# MCU.net
KiCad netlist of a schematic drawn in Altium Designer
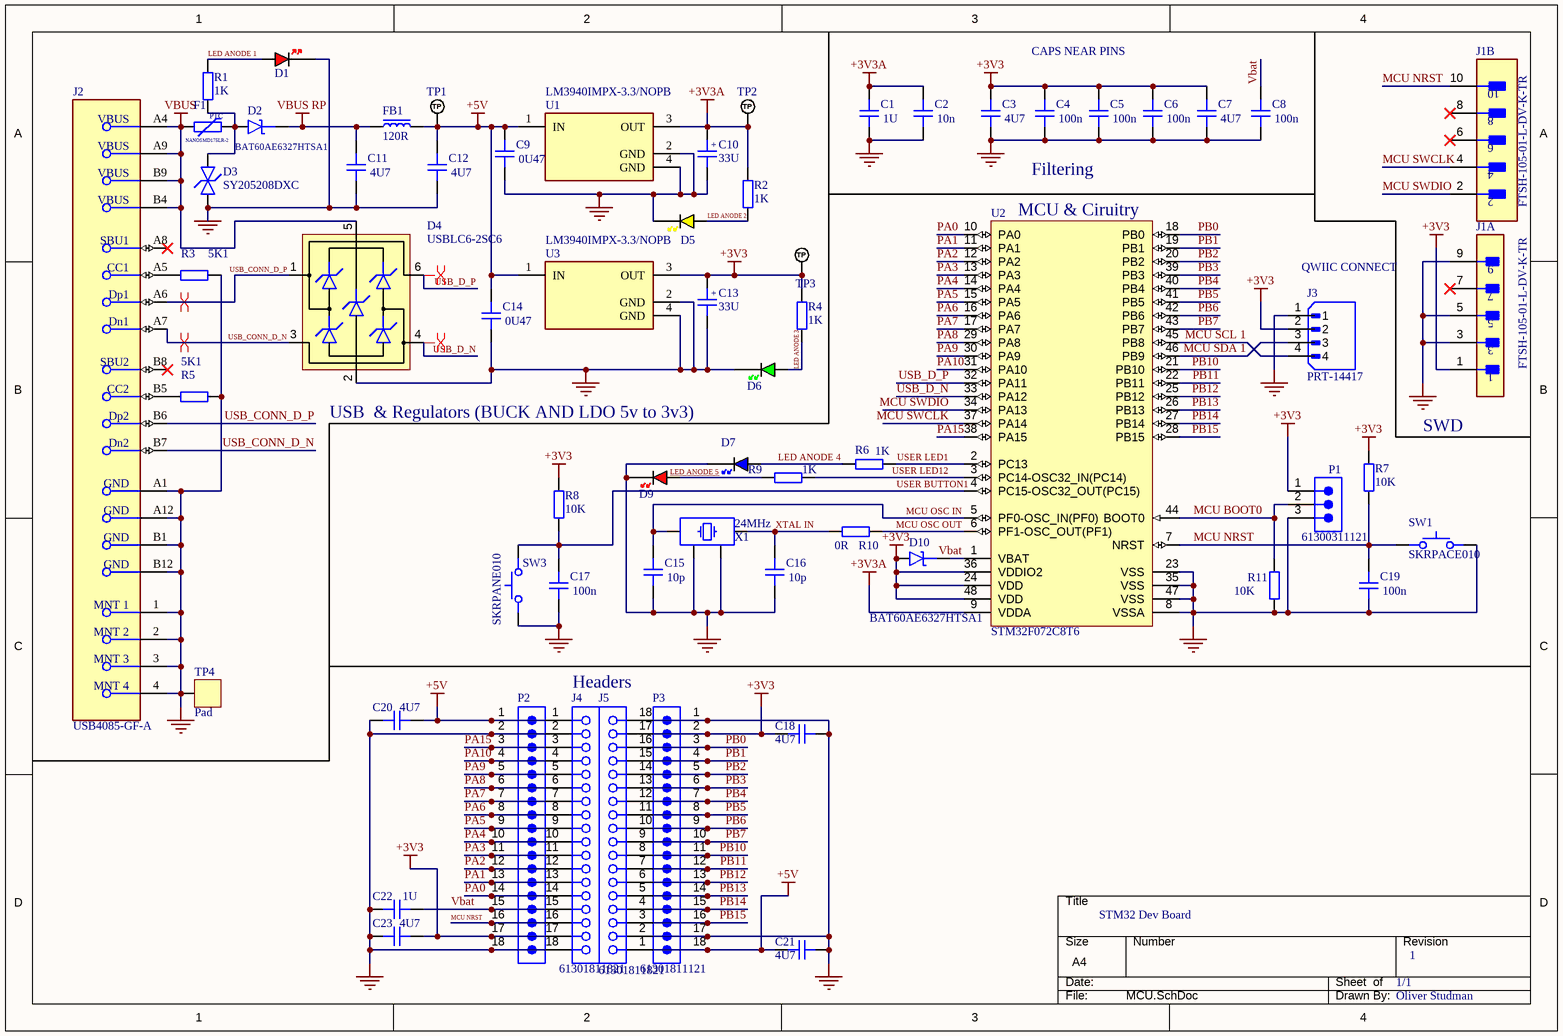
[diagram p0: MCU.SchDoc]

(export (version "E")
  (design (tool "Eeschema 10.0.6"))
  (components
    (comp (ref "C1")
      (value "1U")
      (footprint "CAP_0603")
      (description "Capacitor SMD 0603")
      (libsource (lib "Schematic-Lib-PhilsLab") (part "CAP_0603"))
    )
    (comp (ref "C2")
      (value "10n")
      (footprint "CAP_0603")
      (description "Capacitor SMD 0603")
      (libsource (lib "Schematic-Lib-PhilsLab") (part "CAP_0603"))
    )
    (comp (ref "C3")
      (value "4U7")
      (footprint "CAP_0603")
      (description "Capacitor SMD 0603")
      (libsource (lib "Schematic-Lib-PhilsLab") (part "CAP_0603"))
    )
    (comp (ref "C4")
      (value "100n")
      (footprint "CAP_0603")
      (description "Capacitor SMD 0603")
      (libsource (lib "Schematic-Lib-PhilsLab") (part "CAP_0603"))
    )
    (comp (ref "C5")
      (value "100n")
      (footprint "CAP_0603")
      (description "Capacitor SMD 0603")
      (libsource (lib "Schematic-Lib-PhilsLab") (part "CAP_0603"))
    )
    (comp (ref "C6")
      (value "100n")
      (footprint "CAP_0603")
      (description "Capacitor SMD 0603")
      (libsource (lib "Schematic-Lib-PhilsLab") (part "CAP_0603"))
    )
    (comp (ref "C7")
      (value "4U7")
      (footprint "CAP_0603")
      (description "Capacitor SMD 0603")
      (libsource (lib "Schematic-Lib-PhilsLab") (part "CAP_0603"))
    )
    (comp (ref "C8")
      (value "100n")
      (footprint "CAP_0603")
      (description "Capacitor SMD 0603")
      (libsource (lib "Schematic-Lib-PhilsLab") (part "CAP_0603"))
    )
    (comp (ref "C9")
      (value "0U47")
      (footprint "CAP_0603")
      (description "Capacitor SMD 0603")
      (libsource (lib "Schematic-Lib-PhilsLab") (part "CAP_0603"))
    )
    (comp (ref "C10")
      (value "33U")
      (footprint "CAP_TANT_0603")
      (description "Capacitor SMD Tantalum 0603")
      (libsource (lib "Schematic-Lib-PhilsLab") (part "CAP_TANT_0603"))
    )
    (comp (ref "C11")
      (value "4U7")
      (footprint "CAP_0603")
      (description "Capacitor SMD 0603")
      (libsource (lib "Schematic-Lib-PhilsLab") (part "CAP_0603"))
    )
    (comp (ref "C12")
      (value "4U7")
      (footprint "CAP_0603")
      (description "Capacitor SMD 0603")
      (libsource (lib "Schematic-Lib-PhilsLab") (part "CAP_0603"))
    )
    (comp (ref "C13")
      (value "33U")
      (footprint "CAP_TANT_0603")
      (description "Capacitor SMD Tantalum 0603")
      (libsource (lib "Schematic-Lib-PhilsLab") (part "CAP_TANT_0603"))
    )
    (comp (ref "C14")
      (value "0U47")
      (footprint "CAP_0603")
      (description "Capacitor SMD 0603")
      (libsource (lib "Schematic-Lib-PhilsLab") (part "CAP_0603"))
    )
    (comp (ref "C15")
      (value "10p")
      (footprint "CAP_0603")
      (description "Capacitor SMD 0603")
      (libsource (lib "Schematic-Lib-PhilsLab") (part "CAP_0603"))
    )
    (comp (ref "C16")
      (value "10p")
      (footprint "CAP_0603")
      (description "Capacitor SMD 0603")
      (libsource (lib "Schematic-Lib-PhilsLab") (part "CAP_0603"))
    )
    (comp (ref "C17")
      (value "100n")
      (footprint "CAP_0603")
      (description "Capacitor SMD 0603")
      (libsource (lib "Schematic-Lib-PhilsLab") (part "CAP_0603"))
    )
    (comp (ref "C18")
      (value "4U7")
      (footprint "CAP_0603")
      (description "Capacitor SMD 0603")
      (libsource (lib "Schematic-Lib-PhilsLab") (part "CAP_0603"))
    )
    (comp (ref "C19")
      (value "100n")
      (footprint "CAP_0603")
      (description "Capacitor SMD 0603")
      (libsource (lib "Schematic-Lib-PhilsLab") (part "CAP_0603"))
    )
    (comp (ref "C20")
      (value "4U7")
      (footprint "CAP_0603")
      (description "Capacitor SMD 0603")
      (libsource (lib "Schematic-Lib-PhilsLab") (part "CAP_0603"))
    )
    (comp (ref "C21")
      (value "4U7")
      (footprint "CAP_0603")
      (description "Capacitor SMD 0603")
      (libsource (lib "Schematic-Lib-PhilsLab") (part "CAP_0603"))
    )
    (comp (ref "C22")
      (value "1U")
      (footprint "CAP_0603")
      (description "Capacitor SMD 0603")
      (libsource (lib "Schematic-Lib-PhilsLab") (part "CAP_0603"))
    )
    (comp (ref "C23")
      (value "4U7")
      (footprint "CAP_0603")
      (description "Capacitor SMD 0603")
      (libsource (lib "Schematic-Lib-PhilsLab") (part "CAP_0603"))
    )
    (comp (ref "D1")
      (value "RED")
      (footprint "LED_0603_RED")
      (description "LED 0603 RED SMD")
      (libsource (lib "Schematic-Lib-PhilsLab") (part "LED_0603_RED"))
    )
    (comp (ref "D2")
      (value "BAT60AE6327HTSA1")
      (footprint "SOD-323")
      (description "Diode Schottky SMD SOD-323")
      (libsource (lib "Schematic-Lib-PhilsLab") (part "D_SCHOTTKY_SOD_323"))
    )
    (comp (ref "D3")
      (value "SY205208DXC")
      (footprint "D_0603")
      (description "Diode TVS / ESD Bidirectional 0603")
      (libsource (lib "Schematic-Lib-PhilsLab") (part "D_TVS_BI_0603"))
    )
    (comp (ref "D4")
      (value "USBLC6-2SC6")
      (footprint "SOT-23-6")
      (description "Low-Capacitance ESD Protection USB")
      (fields (field (name "MANUFACTURER") "STMicroelectronics"))
      (libsource (lib "Schematic-Lib-PhilsLab") (part "USBLC6-2SC6"))
    )
    (comp (ref "D5")
      (value "YELLOW")
      (footprint "LED_0603_YELLOW")
      (description "LED 0603 YELLOW SMD")
      (libsource (lib "Schematic-Lib-PhilsLab") (part "LED_0603_YELLOW"))
    )
    (comp (ref "D6")
      (value "GREEN")
      (footprint "LED_0603_GREEN")
      (description "LED 0603 GREEN SMD")
      (libsource (lib "Schematic-Lib-PhilsLab") (part "LED_0603_GREEN"))
    )
    (comp (ref "D7")
      (value "BLUE")
      (footprint "LED_0603_BLUE")
      (description "LED 0603 BLUE SMD")
      (libsource (lib "Schematic-Lib-PhilsLab") (part "LED_0603_BLUE"))
    )
    (comp (ref "D9")
      (value "RED")
      (footprint "LED_0603_RED")
      (description "LED 0603 RED SMD")
      (libsource (lib "Schematic-Lib-PhilsLab") (part "LED_0603_RED"))
    )
    (comp (ref "D10")
      (value "BAT60AE6327HTSA1")
      (footprint "SOD-323")
      (description "Diode Schottky SMD SOD-323")
      (libsource (lib "Schematic-Lib-PhilsLab") (part "D_SCHOTTKY_SOD_323"))
    )
    (comp (ref "F1")
      (value "NANOSMD175LR-2")
      (footprint "FUSE_1206")
      (description "Fuse PPTC SMD 1206")
      (libsource (lib "Schematic-Lib-PhilsLab") (part "FUSE_PPTC_1206"))
    )
    (comp (ref "FB1")
      (value "120R")
      (footprint "FB_0603")
      (description "Ferrite Bead SMD 0603")
      (libsource (lib "Schematic-Lib-PhilsLab") (part "FB_0603"))
    )
    (comp (ref "J1")
      (value "FTSH-105-01-L-DV-K-TR")
      (footprint "FP-FTSH-105-01-L-DV-K-TR-MFG")
      (description "CONN HEADER SMD 10POS 1.27MM")
      (libsource (lib "Altium Content Vault") (part "cf1cfb4cb1e82ff90bf040e1afc05ac"))
    )
    (comp (ref "J2")
      (value "USB4085-GF-A")
      (footprint "FP-USB4085-GF-A-MFG")
      (description "CONN RCPT USB2.0 TYPE C 24POS RA")
      (libsource (lib "Altium Content Vault") (part "10fa745527c8b974685cbca3c197132"))
    )
    (comp (ref "J3")
      (value "PRT-14417")
      (footprint "SPARKFUN_PRT-14417")
      (description "QWIIC JST CONNECTOR - SMD 4-PIN")
      (fields (field (name "MF") "SparkFun Electronics"))
      (libsource (lib "Private") (part "PRT-14417"))
    )
    (comp (ref "J4")
      (value "61301811821")
      (footprint "61301811821")
      (libsource (lib "Altium Content Vault") (part "Header_Female_1R_18P"))
    )
    (comp (ref "J5")
      (value "61301811821")
      (footprint "61301811821")
      (libsource (lib "Altium Content Vault") (part "Header_Female_1R_18P"))
    )
    (comp (ref "P1")
      (value "61300311121")
      (footprint "61300311121")
      (libsource (lib "Altium Content Vault") (part "Header_Male_1R_03P"))
    )
    (comp (ref "P2")
      (value "61301811121")
      (footprint "61301811121")
      (libsource (lib "Altium Content Vault") (part "Header_Male_1R_18P"))
    )
    (comp (ref "P3")
      (value "61301811121")
      (footprint "61301811121")
      (libsource (lib "Altium Content Vault") (part "Header_Male_1R_18P"))
    )
    (comp (ref "R1")
      (value "1K")
      (footprint "RES_0603")
      (description "Resistor SMD 0603")
      (libsource (lib "Schematic-Lib-PhilsLab") (part "RES_0603"))
    )
    (comp (ref "R2")
      (value "1K")
      (footprint "RES_0603")
      (description "Resistor SMD 0603")
      (libsource (lib "Schematic-Lib-PhilsLab") (part "RES_0603"))
    )
    (comp (ref "R3")
      (value "5K1")
      (footprint "RES_0603")
      (description "Resistor SMD 0603")
      (libsource (lib "Schematic-Lib-PhilsLab") (part "RES_0603"))
    )
    (comp (ref "R4")
      (value "1K")
      (footprint "RES_0603")
      (description "Resistor SMD 0603")
      (libsource (lib "Schematic-Lib-PhilsLab") (part "RES_0603"))
    )
    (comp (ref "R5")
      (value "5K1")
      (footprint "RES_0603")
      (description "Resistor SMD 0603")
      (libsource (lib "Schematic-Lib-PhilsLab") (part "RES_0603"))
    )
    (comp (ref "R6")
      (value "1K")
      (footprint "RES_0603")
      (description "Resistor SMD 0603")
      (libsource (lib "Schematic-Lib-PhilsLab") (part "RES_0603"))
    )
    (comp (ref "R7")
      (value "10K")
      (footprint "RES_0603")
      (description "Resistor SMD 0603")
      (libsource (lib "Schematic-Lib-PhilsLab") (part "RES_0603"))
    )
    (comp (ref "R8")
      (value "10K")
      (footprint "RES_0603")
      (description "Resistor SMD 0603")
      (libsource (lib "Schematic-Lib-PhilsLab") (part "RES_0603"))
    )
    (comp (ref "R9")
      (value "1K")
      (footprint "RES_0603")
      (description "Resistor SMD 0603")
      (libsource (lib "Schematic-Lib-PhilsLab") (part "RES_0603"))
    )
    (comp (ref "R10")
      (value "0R")
      (footprint "RES_0603")
      (description "Resistor SMD 0603")
      (libsource (lib "Schematic-Lib-PhilsLab") (part "RES_0603"))
    )
    (comp (ref "R11")
      (value "10K")
      (footprint "RES_0603")
      (description "Resistor SMD 0603")
      (libsource (lib "Schematic-Lib-PhilsLab") (part "RES_0603"))
    )
    (comp (ref "SW1")
      (value "SKRPACE010")
      (footprint "SKRPANE010")
      (description "Tactile Switch SMD SPST")
      (fields
        (field (name "MANUFACTURER") "Alps Alpine")
        (field (name "MANUFACTURER PART NUMBER") "SKRPANE010")
      )
      (libsource (lib "Schematic-Lib-PhilsLab") (part "SKRPANE010"))
    )
    (comp (ref "SW3")
      (value "SKRPANE010")
      (footprint "SKRPANE010")
      (description "Tactile Switch SMD SPST")
      (fields (field (name "MANUFACTURER") "Alps Alpine"))
      (libsource (lib "Schematic-Lib-PhilsLab") (part "SKRPANE010"))
    )
    (comp (ref "TP1")
      (value "TP_NOBOM")
      (footprint "PAD_RND_1MM")
      (description "Test Point Round 1mm (NO BOM)")
      (libsource (lib "Schematic-Lib-PhilsLab") (part "TEST_POINT_RND_1MM"))
    )
    (comp (ref "TP2")
      (value "TP_NOBOM")
      (footprint "PAD_RND_1MM")
      (description "Test Point Round 1mm (NO BOM)")
      (libsource (lib "Schematic-Lib-PhilsLab") (part "TEST_POINT_RND_1MM"))
    )
    (comp (ref "TP3")
      (value "TP_NOBOM")
      (footprint "PAD_RND_1MM")
      (description "Test Point Round 1mm (NO BOM)")
      (libsource (lib "Schematic-Lib-PhilsLab") (part "TEST_POINT_RND_1MM"))
    )
    (comp (ref "TP4")
      (value "Pad")
      (footprint "PAD_SQ_2MM")
      (description "Test Point Square 2mm")
      (libsource (lib "Schematic-Lib-PhilsLab") (part "PAD_SQ_2MM"))
    )
    (comp (ref "U1")
      (value "LM3940IMPX-3.3/NOPB")
      (footprint "FP-DCY0004A-MFG")
      (description "IC REG LINEAR 3.3V 1A SOT223-4")
      (libsource (lib "Altium Content Vault") (part "c31ed432f589313beb2aec2175fc138"))
    )
    (comp (ref "U2")
      (value "STM32F072C8T6")
      (footprint "STM-LQFP48_M")
      (fields (field (name "MANUFACTURER") "STMicroelectronics"))
      (libsource (lib "Altium Content Vault") (part "MC-ARM-STM32F07X-LQFP48"))
    )
    (comp (ref "U3")
      (value "LM3940IMPX-3.3/NOPB")
      (footprint "FP-DCY0004A-MFG")
      (description "IC REG LINEAR 3.3V 1A SOT223-4")
      (libsource (lib "Altium Content Vault") (part "c31ed432f589313beb2aec2175fc138"))
    )
    (comp (ref "X1")
      (value "24MHz")
      (footprint "XTAL_3225")
      (description "Crystal SMD 24MHz 10PPM 7pF 3225")
      (fields
        (field (name "MANUFACTURER") "Epson")
        (field (name "MANUFACTURER PART NUMBER") "TSX-3225 24.0000MF15X-AC")
      )
      (libsource (lib "Schematic-Lib-PhilsLab") (part "TSX-3225_24.0000MF15X-AC"))
    )
  )
  (nets
    (net (code "1") (name "+3V3") (class "Default")
      (node (ref "C13") (pin "A") (pinfunction "A_A") (pintype "passive"))
      (node (ref "C18") (pin "1") (pinfunction "1_1") (pintype "passive"))
      (node (ref "C23") (pin "1") (pinfunction "1_1") (pintype "passive"))
      (node (ref "C3") (pin "2") (pinfunction "2_2") (pintype "passive"))
      (node (ref "C4") (pin "2") (pinfunction "2_2") (pintype "passive"))
      (node (ref "C5") (pin "2") (pinfunction "2_2") (pintype "passive"))
      (node (ref "C6") (pin "2") (pinfunction "2_2") (pintype "passive"))
      (node (ref "C7") (pin "2") (pinfunction "2_2") (pintype "passive"))
      (node (ref "D10") (pin "A") (pinfunction "A_A") (pintype "passive"))
      (node (ref "J1") (pin "1") (pinfunction "1_1") (pintype "passive"))
      (node (ref "J3") (pin "2") (pinfunction "2_2") (pintype "passive"))
      (node (ref "J4") (pin "17") (pinfunction "17_17") (pintype "passive"))
      (node (ref "J5") (pin "17") (pinfunction "17_17") (pintype "passive"))
      (node (ref "P1") (pin "1") (pinfunction "1_1") (pintype "passive"))
      (node (ref "P2") (pin "17") (pinfunction "17_17") (pintype "passive"))
      (node (ref "P3") (pin "2") (pinfunction "2_2") (pintype "passive"))
      (node (ref "R4") (pin "2") (pinfunction "2_2") (pintype "passive"))
      (node (ref "R7") (pin "2") (pinfunction "2_2") (pintype "passive"))
      (node (ref "R8") (pin "2") (pinfunction "2_2") (pintype "passive"))
      (node (ref "TP3") (pin "1") (pinfunction "TP_1") (pintype "passive"))
      (node (ref "U2") (pin "24") (pinfunction "VDD_24") (pintype "power_in"))
      (node (ref "U2") (pin "36") (pinfunction "VDDIO2_36") (pintype "power_in"))
      (node (ref "U2") (pin "48") (pinfunction "VDD_48") (pintype "power_in"))
      (node (ref "U3") (pin "3") (pinfunction "OUT_3") (pintype "passive"))
    )
    (net (code "2") (name "+3V3A") (class "Default")
      (node (ref "C1") (pin "2") (pinfunction "2_2") (pintype "passive"))
      (node (ref "C10") (pin "A") (pinfunction "A_A") (pintype "passive"))
      (node (ref "C2") (pin "2") (pinfunction "2_2") (pintype "passive"))
      (node (ref "R2") (pin "2") (pinfunction "2_2") (pintype "passive"))
      (node (ref "TP2") (pin "1") (pinfunction "TP_1") (pintype "passive"))
      (node (ref "U1") (pin "3") (pinfunction "OUT_3") (pintype "passive"))
      (node (ref "U2") (pin "9") (pinfunction "VDDA_9") (pintype "power_in"))
    )
    (net (code "3") (name "+5V") (class "Default")
      (node (ref "C12") (pin "2") (pinfunction "2_2") (pintype "passive"))
      (node (ref "C14") (pin "2") (pinfunction "2_2") (pintype "passive"))
      (node (ref "C20") (pin "1") (pinfunction "1_1") (pintype "passive"))
      (node (ref "C21") (pin "1") (pinfunction "1_1") (pintype "passive"))
      (node (ref "C9") (pin "2") (pinfunction "2_2") (pintype "passive"))
      (node (ref "FB1") (pin "2") (pinfunction "2_2") (pintype "passive"))
      (node (ref "J4") (pin "1") (pinfunction "1_1") (pintype "passive"))
      (node (ref "J5") (pin "1") (pinfunction "1_1") (pintype "passive"))
      (node (ref "P2") (pin "1") (pinfunction "1_1") (pintype "passive"))
      (node (ref "P3") (pin "18") (pinfunction "18_18") (pintype "passive"))
      (node (ref "TP1") (pin "1") (pinfunction "TP_1") (pintype "passive"))
      (node (ref "U1") (pin "1") (pinfunction "IN_1") (pintype "power_in"))
      (node (ref "U3") (pin "1") (pinfunction "IN_1") (pintype "power_in"))
    )
    (net (code "4") (name "/LED ANODE 1") (class "Default")
      (node (ref "D1") (pin "A") (pinfunction "A_A") (pintype "passive"))
      (node (ref "R1") (pin "2") (pinfunction "2_2") (pintype "passive"))
    )
    (net (code "5") (name "/LED ANODE 2") (class "Default")
      (node (ref "D5") (pin "A") (pinfunction "A_A") (pintype "passive"))
      (node (ref "R2") (pin "1") (pinfunction "1_1") (pintype "passive"))
    )
    (net (code "6") (name "/LED ANODE 3") (class "Default")
      (node (ref "D6") (pin "A") (pinfunction "A_A") (pintype "passive"))
      (node (ref "R4") (pin "1") (pinfunction "1_1") (pintype "passive"))
    )
    (net (code "7") (name "/LED ANODE 4") (class "Default")
      (node (ref "D7") (pin "A") (pinfunction "A_A") (pintype "passive"))
      (node (ref "R6") (pin "1") (pinfunction "1_1") (pintype "passive"))
    )
    (net (code "8") (name "/LED ANODE 5") (class "Default")
      (node (ref "D9") (pin "A") (pinfunction "A_A") (pintype "passive"))
      (node (ref "R9") (pin "1") (pinfunction "1_1") (pintype "passive"))
    )
    (net (code "9") (name "/MCU BOOT0") (class "Default")
      (node (ref "P1") (pin "2") (pinfunction "2_2") (pintype "passive"))
      (node (ref "R11") (pin "2") (pinfunction "2_2") (pintype "passive"))
      (node (ref "U2") (pin "44") (pinfunction "BOOT0_44") (pintype "input"))
    )
    (net (code "10") (name "/MCU NRST") (class "Default")
      (node (ref "C19") (pin "2") (pinfunction "2_2") (pintype "passive"))
      (node (ref "J1") (pin "10") (pinfunction "10_10") (pintype "passive"))
      (node (ref "J4") (pin "16") (pinfunction "16_16") (pintype "passive"))
      (node (ref "P2") (pin "16") (pinfunction "16_16") (pintype "passive"))
      (node (ref "R7") (pin "1") (pinfunction "1_1") (pintype "passive"))
      (node (ref "SW1") (pin "12") (pintype "passive"))
      (node (ref "U2") (pin "7") (pinfunction "NRST_7") (pintype "bidirectional"))
    )
    (net (code "11") (name "/MCU OSC IN") (class "Default")
      (node (ref "C15") (pin "2") (pinfunction "2_2") (pintype "passive"))
      (node (ref "U2") (pin "5") (pinfunction "PF0-OSC_IN(PF0)_5") (pintype "bidirectional"))
      (node (ref "X1") (pin "1") (pinfunction "1_1") (pintype "passive"))
    )
    (net (code "12") (name "/MCU OSC OUT") (class "Default")
      (node (ref "R10") (pin "1") (pinfunction "1_1") (pintype "passive"))
      (node (ref "U2") (pin "6") (pinfunction "PF1-OSC_OUT(PF1)_6") (pintype "bidirectional"))
    )
    (net (code "13") (name "/MCU SCL 1") (class "Default")
      (node (ref "J3") (pin "4") (pinfunction "4_4") (pintype "passive"))
      (node (ref "U2") (pin "45") (pinfunction "PB8_45") (pintype "bidirectional"))
    )
    (net (code "14") (name "/MCU SDA 1") (class "Default")
      (node (ref "J3") (pin "3") (pinfunction "3_3") (pintype "passive"))
      (node (ref "U2") (pin "46") (pinfunction "PB9_46") (pintype "bidirectional"))
    )
    (net (code "15") (name "/MCU SWCLK") (class "Default")
      (node (ref "J1") (pin "4") (pinfunction "4_4") (pintype "passive"))
      (node (ref "U2") (pin "37") (pinfunction "PA14_37") (pintype "bidirectional"))
    )
    (net (code "16") (name "/MCU SWDIO") (class "Default")
      (node (ref "J1") (pin "2") (pinfunction "2_2") (pintype "passive"))
      (node (ref "U2") (pin "34") (pinfunction "PA13_34") (pintype "bidirectional"))
    )
    (net (code "17") (name "/PA0") (class "Default")
      (node (ref "J4") (pin "14") (pinfunction "14_14") (pintype "passive"))
      (node (ref "P2") (pin "14") (pinfunction "14_14") (pintype "passive"))
      (node (ref "U2") (pin "10") (pinfunction "PA0_10") (pintype "bidirectional"))
    )
    (net (code "18") (name "/PA1") (class "Default")
      (node (ref "J4") (pin "13") (pinfunction "13_13") (pintype "passive"))
      (node (ref "P2") (pin "13") (pinfunction "13_13") (pintype "passive"))
      (node (ref "U2") (pin "11") (pinfunction "PA1_11") (pintype "bidirectional"))
    )
    (net (code "19") (name "/PA2") (class "Default")
      (node (ref "J4") (pin "12") (pinfunction "12_12") (pintype "passive"))
      (node (ref "P2") (pin "12") (pinfunction "12_12") (pintype "passive"))
      (node (ref "U2") (pin "12") (pinfunction "PA2_12") (pintype "bidirectional"))
    )
    (net (code "20") (name "/PA3") (class "Default")
      (node (ref "J4") (pin "11") (pinfunction "11_11") (pintype "passive"))
      (node (ref "P2") (pin "11") (pinfunction "11_11") (pintype "passive"))
      (node (ref "U2") (pin "13") (pinfunction "PA3_13") (pintype "bidirectional"))
    )
    (net (code "21") (name "/PA4") (class "Default")
      (node (ref "J4") (pin "10") (pinfunction "10_10") (pintype "passive"))
      (node (ref "P2") (pin "10") (pinfunction "10_10") (pintype "passive"))
      (node (ref "U2") (pin "14") (pinfunction "PA4_14") (pintype "bidirectional"))
    )
    (net (code "22") (name "/PA5") (class "Default")
      (node (ref "J4") (pin "9") (pinfunction "9_9") (pintype "passive"))
      (node (ref "P2") (pin "9") (pinfunction "9_9") (pintype "passive"))
      (node (ref "U2") (pin "15") (pinfunction "PA5_15") (pintype "bidirectional"))
    )
    (net (code "23") (name "/PA6") (class "Default")
      (node (ref "J4") (pin "8") (pinfunction "8_8") (pintype "passive"))
      (node (ref "P2") (pin "8") (pinfunction "8_8") (pintype "passive"))
      (node (ref "U2") (pin "16") (pinfunction "PA6_16") (pintype "bidirectional"))
    )
    (net (code "24") (name "/PA7") (class "Default")
      (node (ref "J4") (pin "7") (pinfunction "7_7") (pintype "passive"))
      (node (ref "P2") (pin "7") (pinfunction "7_7") (pintype "passive"))
      (node (ref "U2") (pin "17") (pinfunction "PA7_17") (pintype "bidirectional"))
    )
    (net (code "25") (name "/PA8") (class "Default")
      (node (ref "J4") (pin "6") (pinfunction "6_6") (pintype "passive"))
      (node (ref "P2") (pin "6") (pinfunction "6_6") (pintype "passive"))
      (node (ref "U2") (pin "29") (pinfunction "PA8_29") (pintype "bidirectional"))
    )
    (net (code "26") (name "/PA9") (class "Default")
      (node (ref "J4") (pin "5") (pinfunction "5_5") (pintype "passive"))
      (node (ref "P2") (pin "5") (pinfunction "5_5") (pintype "passive"))
      (node (ref "U2") (pin "30") (pinfunction "PA9_30") (pintype "bidirectional"))
    )
    (net (code "27") (name "/PA10") (class "Default")
      (node (ref "J4") (pin "4") (pinfunction "4_4") (pintype "passive"))
      (node (ref "P2") (pin "4") (pinfunction "4_4") (pintype "passive"))
      (node (ref "U2") (pin "31") (pinfunction "PA10_31") (pintype "bidirectional"))
    )
    (net (code "28") (name "/PA15") (class "Default")
      (node (ref "J4") (pin "3") (pinfunction "3_3") (pintype "passive"))
      (node (ref "P2") (pin "3") (pinfunction "3_3") (pintype "passive"))
      (node (ref "U2") (pin "38") (pinfunction "PA15_38") (pintype "bidirectional"))
    )
    (net (code "29") (name "/PB0") (class "Default")
      (node (ref "J5") (pin "16") (pinfunction "16_16") (pintype "passive"))
      (node (ref "P3") (pin "3") (pinfunction "3_3") (pintype "passive"))
      (node (ref "U2") (pin "18") (pinfunction "PB0_18") (pintype "bidirectional"))
    )
    (net (code "30") (name "/PB1") (class "Default")
      (node (ref "J5") (pin "15") (pinfunction "15_15") (pintype "passive"))
      (node (ref "P3") (pin "4") (pinfunction "4_4") (pintype "passive"))
      (node (ref "U2") (pin "19") (pinfunction "PB1_19") (pintype "bidirectional"))
    )
    (net (code "31") (name "/PB2") (class "Default")
      (node (ref "J5") (pin "14") (pinfunction "14_14") (pintype "passive"))
      (node (ref "P3") (pin "5") (pinfunction "5_5") (pintype "passive"))
      (node (ref "U2") (pin "20") (pinfunction "PB2_20") (pintype "bidirectional"))
    )
    (net (code "32") (name "/PB3") (class "Default")
      (node (ref "J5") (pin "13") (pinfunction "13_13") (pintype "passive"))
      (node (ref "P3") (pin "6") (pinfunction "6_6") (pintype "passive"))
      (node (ref "U2") (pin "39") (pinfunction "PB3_39") (pintype "bidirectional"))
    )
    (net (code "33") (name "/PB4") (class "Default")
      (node (ref "J5") (pin "12") (pinfunction "12_12") (pintype "passive"))
      (node (ref "P3") (pin "7") (pinfunction "7_7") (pintype "passive"))
      (node (ref "U2") (pin "40") (pinfunction "PB4_40") (pintype "bidirectional"))
    )
    (net (code "34") (name "/PB5") (class "Default")
      (node (ref "J5") (pin "11") (pinfunction "11_11") (pintype "passive"))
      (node (ref "P3") (pin "8") (pinfunction "8_8") (pintype "passive"))
      (node (ref "U2") (pin "41") (pinfunction "PB5_41") (pintype "bidirectional"))
    )
    (net (code "35") (name "/PB6") (class "Default")
      (node (ref "J5") (pin "10") (pinfunction "10_10") (pintype "passive"))
      (node (ref "P3") (pin "9") (pinfunction "9_9") (pintype "passive"))
      (node (ref "U2") (pin "42") (pinfunction "PB6_42") (pintype "bidirectional"))
    )
    (net (code "36") (name "/PB7") (class "Default")
      (node (ref "J5") (pin "9") (pinfunction "9_9") (pintype "passive"))
      (node (ref "P3") (pin "10") (pinfunction "10_10") (pintype "passive"))
      (node (ref "U2") (pin "43") (pinfunction "PB7_43") (pintype "bidirectional"))
    )
    (net (code "37") (name "/PB10") (class "Default")
      (node (ref "J5") (pin "8") (pinfunction "8_8") (pintype "passive"))
      (node (ref "P3") (pin "11") (pinfunction "11_11") (pintype "passive"))
      (node (ref "U2") (pin "21") (pinfunction "PB10_21") (pintype "bidirectional"))
    )
    (net (code "38") (name "/PB11") (class "Default")
      (node (ref "J5") (pin "7") (pinfunction "7_7") (pintype "passive"))
      (node (ref "P3") (pin "12") (pinfunction "12_12") (pintype "passive"))
      (node (ref "U2") (pin "22") (pinfunction "PB11_22") (pintype "bidirectional"))
    )
    (net (code "39") (name "/PB12") (class "Default")
      (node (ref "J5") (pin "6") (pinfunction "6_6") (pintype "passive"))
      (node (ref "P3") (pin "13") (pinfunction "13_13") (pintype "passive"))
      (node (ref "U2") (pin "25") (pinfunction "PB12_25") (pintype "bidirectional"))
    )
    (net (code "40") (name "/PB13") (class "Default")
      (node (ref "J5") (pin "5") (pinfunction "5_5") (pintype "passive"))
      (node (ref "P3") (pin "14") (pinfunction "14_14") (pintype "passive"))
      (node (ref "U2") (pin "26") (pinfunction "PB13_26") (pintype "bidirectional"))
    )
    (net (code "41") (name "/PB14") (class "Default")
      (node (ref "J5") (pin "4") (pinfunction "4_4") (pintype "passive"))
      (node (ref "P3") (pin "15") (pinfunction "15_15") (pintype "passive"))
      (node (ref "U2") (pin "27") (pinfunction "PB14_27") (pintype "bidirectional"))
    )
    (net (code "42") (name "/PB15") (class "Default")
      (node (ref "J5") (pin "3") (pinfunction "3_3") (pintype "passive"))
      (node (ref "P3") (pin "16") (pinfunction "16_16") (pintype "passive"))
      (node (ref "U2") (pin "28") (pinfunction "PB15_28") (pintype "bidirectional"))
    )
    (net (code "43") (name "/USB_CONN_D_N") (class "Default")
      (node (ref "D4") (pin "3") (pinfunction "IO2_3") (pintype "bidirectional"))
      (node (ref "J2") (pin "A7") (pinfunction "Dn1_A7") (pintype "bidirectional"))
      (node (ref "J2") (pin "B7") (pinfunction "Dn2_B7") (pintype "bidirectional"))
    )
    (net (code "44") (name "/USB_CONN_D_P") (class "Default")
      (node (ref "D4") (pin "1") (pinfunction "IO1_1") (pintype "bidirectional"))
      (node (ref "J2") (pin "A6") (pinfunction "Dp1_A6") (pintype "bidirectional"))
      (node (ref "J2") (pin "B6") (pinfunction "Dp2_B6") (pintype "bidirectional"))
    )
    (net (code "45") (name "/USB_D_N") (class "Default")
      (node (ref "D4") (pin "4") (pinfunction "IO2_4") (pintype "bidirectional"))
      (node (ref "U2") (pin "33") (pinfunction "PA12_33") (pintype "bidirectional"))
    )
    (net (code "46") (name "/USB_D_P") (class "Default")
      (node (ref "D4") (pin "6") (pinfunction "IO1_6") (pintype "bidirectional"))
      (node (ref "U2") (pin "32") (pinfunction "PA11_32") (pintype "bidirectional"))
    )
    (net (code "47") (name "/USER BUTTON1") (class "Default")
      (node (ref "C17") (pin "2") (pinfunction "2_2") (pintype "passive"))
      (node (ref "R8") (pin "1") (pinfunction "1_1") (pintype "passive"))
      (node (ref "SW3") (pin "34") (pintype "passive"))
      (node (ref "U2") (pin "4") (pinfunction "PC15-OSC32_OUT(PC15)_4") (pintype "bidirectional"))
    )
    (net (code "48") (name "/USER LED1") (class "Default")
      (node (ref "R6") (pin "2") (pinfunction "2_2") (pintype "passive"))
      (node (ref "U2") (pin "2") (pinfunction "PC13_2") (pintype "bidirectional"))
    )
    (net (code "49") (name "/USER LED12") (class "Default")
      (node (ref "R9") (pin "2") (pinfunction "2_2") (pintype "passive"))
      (node (ref "U2") (pin "3") (pinfunction "PC14-OSC32_IN(PC14)_3") (pintype "bidirectional"))
    )
    (net (code "50") (name "/Vbat") (class "Default")
      (node (ref "C22") (pin "1") (pinfunction "1_1") (pintype "passive"))
      (node (ref "C8") (pin "2") (pinfunction "2_2") (pintype "passive"))
      (node (ref "D10") (pin "K") (pinfunction "K_K") (pintype "passive"))
      (node (ref "J4") (pin "15") (pinfunction "15_15") (pintype "passive"))
      (node (ref "P2") (pin "15") (pinfunction "15_15") (pintype "passive"))
      (node (ref "U2") (pin "1") (pinfunction "VBAT_1") (pintype "power_in"))
    )
    (net (code "51") (name "/XTAL IN") (class "Default")
      (node (ref "C16") (pin "2") (pinfunction "2_2") (pintype "passive"))
      (node (ref "R10") (pin "2") (pinfunction "2_2") (pintype "passive"))
      (node (ref "X1") (pin "3") (pinfunction "3_3") (pintype "passive"))
    )
    (net (code "52") (name "GND") (class "Default")
      (node (ref "C1") (pin "1") (pinfunction "1_1") (pintype "passive"))
      (node (ref "C10") (pin "K") (pinfunction "K_K") (pintype "passive"))
      (node (ref "C11") (pin "1") (pinfunction "1_1") (pintype "passive"))
      (node (ref "C12") (pin "1") (pinfunction "1_1") (pintype "passive"))
      (node (ref "C13") (pin "K") (pinfunction "K_K") (pintype "passive"))
      (node (ref "C14") (pin "1") (pinfunction "1_1") (pintype "passive"))
      (node (ref "C15") (pin "1") (pinfunction "1_1") (pintype "passive"))
      (node (ref "C16") (pin "1") (pinfunction "1_1") (pintype "passive"))
      (node (ref "C17") (pin "1") (pinfunction "1_1") (pintype "passive"))
      (node (ref "C18") (pin "2") (pinfunction "2_2") (pintype "passive"))
      (node (ref "C19") (pin "1") (pinfunction "1_1") (pintype "passive"))
      (node (ref "C2") (pin "1") (pinfunction "1_1") (pintype "passive"))
      (node (ref "C20") (pin "2") (pinfunction "2_2") (pintype "passive"))
      (node (ref "C21") (pin "2") (pinfunction "2_2") (pintype "passive"))
      (node (ref "C22") (pin "2") (pinfunction "2_2") (pintype "passive"))
      (node (ref "C23") (pin "2") (pinfunction "2_2") (pintype "passive"))
      (node (ref "C3") (pin "1") (pinfunction "1_1") (pintype "passive"))
      (node (ref "C4") (pin "1") (pinfunction "1_1") (pintype "passive"))
      (node (ref "C5") (pin "1") (pinfunction "1_1") (pintype "passive"))
      (node (ref "C6") (pin "1") (pinfunction "1_1") (pintype "passive"))
      (node (ref "C7") (pin "1") (pinfunction "1_1") (pintype "passive"))
      (node (ref "C8") (pin "1") (pinfunction "1_1") (pintype "passive"))
      (node (ref "C9") (pin "1") (pinfunction "1_1") (pintype "passive"))
      (node (ref "D1") (pin "K") (pinfunction "K_K") (pintype "passive"))
      (node (ref "D3") (pin "A") (pinfunction "A_A") (pintype "passive"))
      (node (ref "D4") (pin "2") (pinfunction "GND_2") (pintype "power_in"))
      (node (ref "D5") (pin "K") (pinfunction "K_K") (pintype "passive"))
      (node (ref "D6") (pin "K") (pinfunction "K_K") (pintype "passive"))
      (node (ref "D7") (pin "K") (pinfunction "K_K") (pintype "passive"))
      (node (ref "D9") (pin "K") (pinfunction "K_K") (pintype "passive"))
      (node (ref "J1") (pin "3") (pinfunction "3_3") (pintype "passive"))
      (node (ref "J1") (pin "5") (pinfunction "5_5") (pintype "passive"))
      (node (ref "J1") (pin "9") (pinfunction "9_9") (pintype "passive"))
      (node (ref "J2") (pin "1") (pinfunction "MNT_1_1") (pintype "passive"))
      (node (ref "J2") (pin "2") (pinfunction "MNT_2_2") (pintype "passive"))
      (node (ref "J2") (pin "3") (pinfunction "MNT_3_3") (pintype "passive"))
      (node (ref "J2") (pin "4") (pinfunction "MNT_4_4") (pintype "passive"))
      (node (ref "J2") (pin "A1") (pinfunction "GND_A1") (pintype "power_in"))
      (node (ref "J2") (pin "A12") (pinfunction "GND_A12") (pintype "power_in"))
      (node (ref "J2") (pin "B1") (pinfunction "GND_B1") (pintype "power_in"))
      (node (ref "J2") (pin "B12") (pinfunction "GND_B12") (pintype "power_in"))
      (node (ref "J3") (pin "1") (pinfunction "1_1") (pintype "passive"))
      (node (ref "J4") (pin "18") (pinfunction "18_18") (pintype "passive"))
      (node (ref "J4") (pin "2") (pinfunction "2_2") (pintype "passive"))
      (node (ref "J5") (pin "18") (pinfunction "18_18") (pintype "passive"))
      (node (ref "J5") (pin "2") (pinfunction "2_2") (pintype "passive"))
      (node (ref "P1") (pin "3") (pinfunction "3_3") (pintype "passive"))
      (node (ref "P2") (pin "18") (pinfunction "18_18") (pintype "passive"))
      (node (ref "P2") (pin "2") (pinfunction "2_2") (pintype "passive"))
      (node (ref "P3") (pin "1") (pinfunction "1_1") (pintype "passive"))
      (node (ref "P3") (pin "17") (pinfunction "17_17") (pintype "passive"))
      (node (ref "R11") (pin "1") (pinfunction "1_1") (pintype "passive"))
      (node (ref "R3") (pin "2") (pinfunction "2_2") (pintype "passive"))
      (node (ref "R5") (pin "1") (pinfunction "1_1") (pintype "passive"))
      (node (ref "SW1") (pin "34") (pintype "passive"))
      (node (ref "SW3") (pin "12") (pintype "passive"))
      (node (ref "TP4") (pin "1") (pinfunction "1_1") (pintype "passive"))
      (node (ref "U1") (pin "2") (pinfunction "GND_2") (pintype "power_in"))
      (node (ref "U1") (pin "4") (pinfunction "GND_4") (pintype "power_in"))
      (node (ref "U2") (pin "23") (pinfunction "VSS_23") (pintype "power_in"))
      (node (ref "U2") (pin "35") (pinfunction "VSS_35") (pintype "power_in"))
      (node (ref "U2") (pin "47") (pinfunction "VSS_47") (pintype "power_in"))
      (node (ref "U2") (pin "8") (pinfunction "VSSA_8") (pintype "power_in"))
      (node (ref "U3") (pin "2") (pinfunction "GND_2") (pintype "power_in"))
      (node (ref "U3") (pin "4") (pinfunction "GND_4") (pintype "power_in"))
      (node (ref "X1") (pin "2") (pinfunction "2_2") (pintype "passive"))
      (node (ref "X1") (pin "4") (pinfunction "4_4") (pintype "passive"))
    )
    (net (code "53") (name "Net-(D2-PadA)") (class "Default")
      (node (ref "D2") (pin "A") (pinfunction "A_A") (pintype "passive"))
      (node (ref "D3") (pin "K") (pinfunction "K_K") (pintype "passive"))
      (node (ref "F1") (pin "2") (pinfunction "2_2") (pintype "passive"))
      (node (ref "R1") (pin "1") (pinfunction "1_1") (pintype "passive"))
    )
    (net (code "54") (name "Net-(J2-CC1)") (class "Default")
      (node (ref "J2") (pin "A5") (pinfunction "CC1_A5") (pintype "bidirectional"))
      (node (ref "R3") (pin "1") (pinfunction "1_1") (pintype "passive"))
    )
    (net (code "55") (name "Net-(J2-CC2)") (class "Default")
      (node (ref "J2") (pin "B5") (pinfunction "CC2_B5") (pintype "bidirectional"))
      (node (ref "R5") (pin "2") (pinfunction "2_2") (pintype "passive"))
    )
    (net (code "56") (name "VBUS") (class "Default")
      (node (ref "D4") (pin "5") (pinfunction "VBUS_5") (pintype "power_in"))
      (node (ref "F1") (pin "1") (pinfunction "1_1") (pintype "passive"))
      (node (ref "J2") (pin "A4") (pinfunction "VBUS_A4") (pintype "power_in"))
      (node (ref "J2") (pin "A9") (pinfunction "VBUS_A9") (pintype "power_in"))
      (node (ref "J2") (pin "B4") (pinfunction "VBUS_B4") (pintype "power_in"))
      (node (ref "J2") (pin "B9") (pinfunction "VBUS_B9") (pintype "power_in"))
    )
    (net (code "57") (name "VBUS RP") (class "Default")
      (node (ref "C11") (pin "2") (pinfunction "2_2") (pintype "passive"))
      (node (ref "D2") (pin "K") (pinfunction "K_K") (pintype "passive"))
      (node (ref "FB1") (pin "1") (pinfunction "1_1") (pintype "passive"))
    )
    (net (code "58") (name "unconnected-(J1-Pad6)") (class "Default")
      (node (ref "J1") (pin "6") (pinfunction "6_6") (pintype "passive+no_connect"))
    )
    (net (code "59") (name "unconnected-(J1-Pad7)") (class "Default")
      (node (ref "J1") (pin "7") (pinfunction "7_7") (pintype "passive+no_connect"))
    )
    (net (code "60") (name "unconnected-(J1-Pad8)") (class "Default")
      (node (ref "J1") (pin "8") (pinfunction "8_8") (pintype "passive+no_connect"))
    )
    (net (code "61") (name "unconnected-(J2-SBU1-PadA8)") (class "Default")
      (node (ref "J2") (pin "A8") (pinfunction "SBU1_A8") (pintype "bidirectional+no_connect"))
    )
    (net (code "62") (name "unconnected-(J2-SBU2-PadB8)") (class "Default")
      (node (ref "J2") (pin "B8") (pinfunction "SBU2_B8") (pintype "bidirectional+no_connect"))
    )
  )
)
